# ESP-01_Breakout.net
KiCad netlist of a schematic drawn in EAGLE
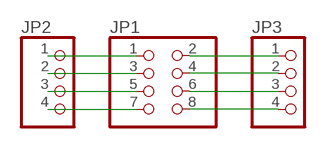
[diagram p0: schematic, sheet 1]

(export (version "E")
  (design (tool "Eeschema 10.0.6"))
  (components
    (comp (ref "JP1")
      (value "PINHD-2X4")
      (footprint "eagle-import:2X04")
      (libsource (lib "eagle-import") (part "PINHD-2X4"))
    )
    (comp (ref "JP2")
      (value "PINHD-1X4")
      (footprint "eagle-import:1X04")
      (libsource (lib "eagle-import") (part "PINHD-1X4"))
    )
    (comp (ref "JP3")
      (value "PINHD-1X4")
      (footprint "eagle-import:1X04")
      (libsource (lib "eagle-import") (part "PINHD-1X4"))
    )
  )
  (nets
    (net (code "1") (name "Net-(JP1-Pad1)") (class "Default")
      (node (ref "JP1") (pin "1") (pinfunction "1_1") (pintype "passive"))
      (node (ref "JP2") (pin "1") (pinfunction "1_1") (pintype "passive"))
    )
    (net (code "2") (name "Net-(JP1-Pad2)") (class "Default")
      (node (ref "JP1") (pin "2") (pinfunction "2_2") (pintype "passive"))
      (node (ref "JP3") (pin "1") (pinfunction "1_1") (pintype "passive"))
    )
    (net (code "3") (name "Net-(JP1-Pad3)") (class "Default")
      (node (ref "JP1") (pin "3") (pinfunction "3_3") (pintype "passive"))
      (node (ref "JP2") (pin "2") (pinfunction "2_2") (pintype "passive"))
    )
    (net (code "4") (name "Net-(JP1-Pad4)") (class "Default")
      (node (ref "JP1") (pin "4") (pinfunction "4_4") (pintype "passive"))
      (node (ref "JP3") (pin "2") (pinfunction "2_2") (pintype "passive"))
    )
    (net (code "5") (name "Net-(JP1-Pad5)") (class "Default")
      (node (ref "JP1") (pin "5") (pinfunction "5_5") (pintype "passive"))
      (node (ref "JP2") (pin "3") (pinfunction "3_3") (pintype "passive"))
    )
    (net (code "6") (name "Net-(JP1-Pad6)") (class "Default")
      (node (ref "JP1") (pin "6") (pinfunction "6_6") (pintype "passive"))
      (node (ref "JP3") (pin "3") (pinfunction "3_3") (pintype "passive"))
    )
    (net (code "7") (name "Net-(JP1-Pad7)") (class "Default")
      (node (ref "JP1") (pin "7") (pinfunction "7_7") (pintype "passive"))
      (node (ref "JP2") (pin "4") (pinfunction "4_4") (pintype "passive"))
    )
    (net (code "8") (name "Net-(JP1-Pad8)") (class "Default")
      (node (ref "JP1") (pin "8") (pinfunction "8_8") (pintype "passive"))
      (node (ref "JP3") (pin "4") (pinfunction "4_4") (pintype "passive"))
    )
  )
)
